# RP2350.net
KiCad netlist of a schematic drawn in Altium Designer
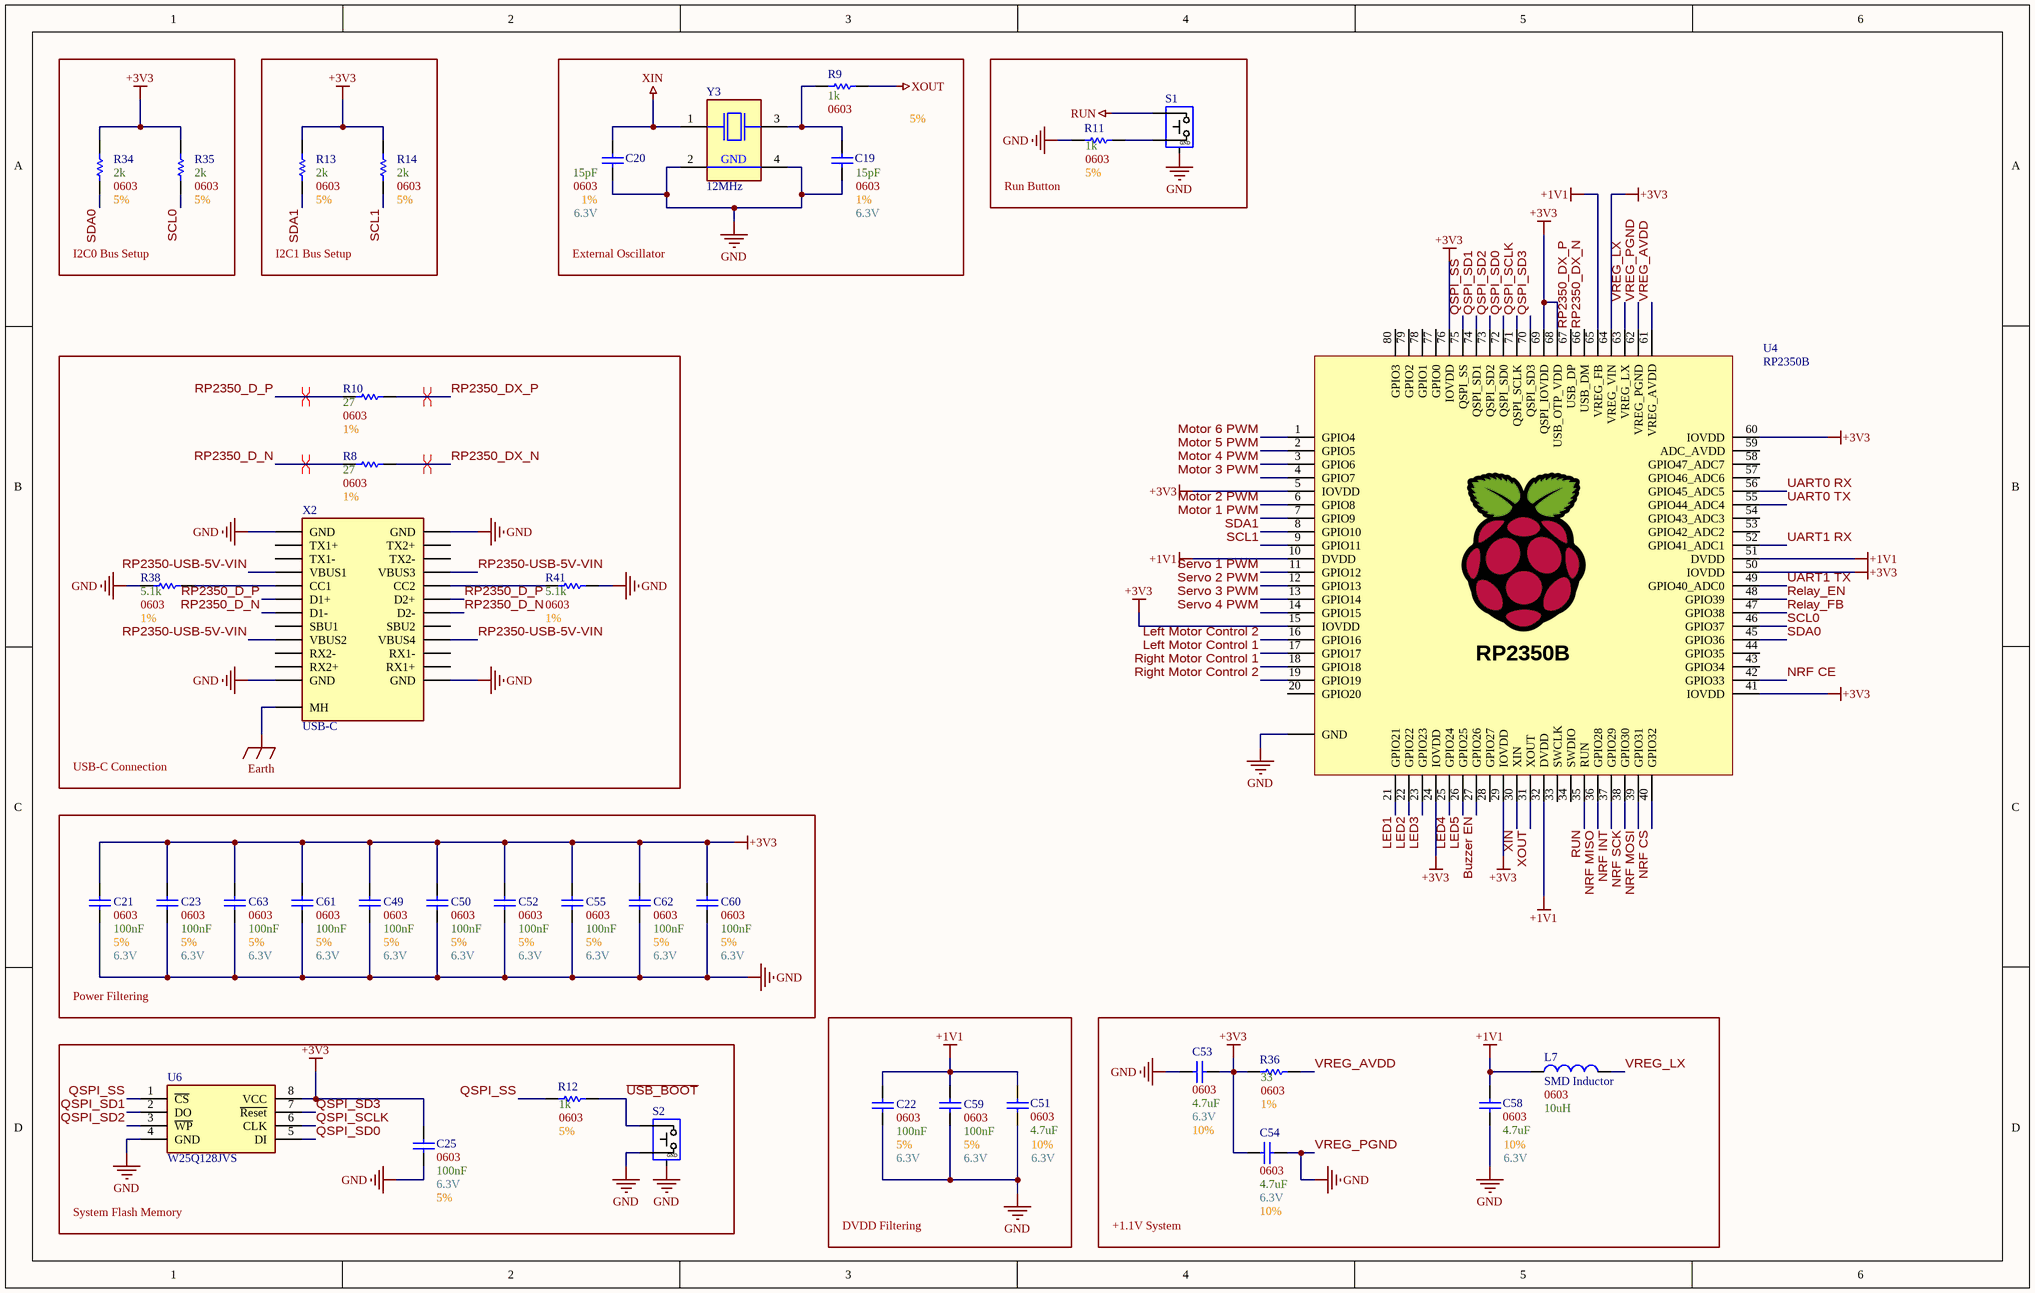
[diagram p0: RP2350.SchDoc]

(export (version "E")
  (design (tool "Eeschema 10.0.6"))
  (components
    (comp (ref "C19")
      (value "[Cap] SMD Nonpolarized")
      (footprint "[Cap] SMD 0603")
      (fields
        (field (name "SIZE PACKAGE") "0603")
        (field (name "CAPACITANCE") "15pF")
        (field (name "VOLTAGE") "6.3V")
        (field (name "TOLERANCE") "1%")
      )
      (libsource (lib "RADM Components") (part "[Cap] SMD Nonpolarized"))
    )
    (comp (ref "C20")
      (value "[Cap] SMD Nonpolarized")
      (footprint "[Cap] SMD 0603")
      (fields
        (field (name "SIZE PACKAGE") "0603")
        (field (name "CAPACITANCE") "15pF")
        (field (name "VOLTAGE") "6.3V")
        (field (name "TOLERANCE") "1%")
      )
      (libsource (lib "RADM Components") (part "[Cap] SMD Nonpolarized"))
    )
    (comp (ref "C21")
      (value "[Cap] SMD Nonpolarized")
      (footprint "[Cap] SMD 0603")
      (fields
        (field (name "SIZE PACKAGE") "0603")
        (field (name "CAPACITANCE") "100nF")
        (field (name "VOLTAGE") "6.3V")
        (field (name "TOLERANCE") "5%")
      )
      (libsource (lib "RADM Components") (part "[Cap] SMD Nonpolarized"))
    )
    (comp (ref "C22")
      (value "[Cap] SMD Nonpolarized")
      (footprint "[Cap] SMD 0603")
      (fields
        (field (name "SIZE PACKAGE") "0603")
        (field (name "CAPACITANCE") "100nF")
        (field (name "VOLTAGE") "6.3V")
        (field (name "TOLERANCE") "5%")
      )
      (libsource (lib "RADM Components") (part "[Cap] SMD Nonpolarized"))
    )
    (comp (ref "C23")
      (value "[Cap] SMD Nonpolarized")
      (footprint "[Cap] SMD 0603")
      (fields
        (field (name "SIZE PACKAGE") "0603")
        (field (name "CAPACITANCE") "100nF")
        (field (name "VOLTAGE") "6.3V")
        (field (name "TOLERANCE") "5%")
      )
      (libsource (lib "RADM Components") (part "[Cap] SMD Nonpolarized"))
    )
    (comp (ref "C25")
      (value "[Cap] SMD Nonpolarized")
      (footprint "[Cap] SMD 0603")
      (fields
        (field (name "SIZE PACKAGE") "0603")
        (field (name "CAPACITANCE") "100nF")
        (field (name "VOLTAGE") "6.3V")
        (field (name "TOLERANCE") "5%")
      )
      (libsource (lib "RADM Components") (part "[Cap] SMD Nonpolarized"))
    )
    (comp (ref "C49")
      (value "[Cap] SMD Nonpolarized")
      (footprint "[Cap] SMD 0603")
      (fields
        (field (name "SIZE PACKAGE") "0603")
        (field (name "CAPACITANCE") "100nF")
        (field (name "VOLTAGE") "6.3V")
        (field (name "TOLERANCE") "5%")
      )
      (libsource (lib "RADM Components") (part "[Cap] SMD Nonpolarized"))
    )
    (comp (ref "C50")
      (value "[Cap] SMD Nonpolarized")
      (footprint "[Cap] SMD 0603")
      (fields
        (field (name "SIZE PACKAGE") "0603")
        (field (name "CAPACITANCE") "100nF")
        (field (name "VOLTAGE") "6.3V")
        (field (name "TOLERANCE") "5%")
      )
      (libsource (lib "RADM Components") (part "[Cap] SMD Nonpolarized"))
    )
    (comp (ref "C51")
      (value "[Cap] SMD Nonpolarized")
      (footprint "[Cap] SMD 0603")
      (fields
        (field (name "SIZE PACKAGE") "0603")
        (field (name "CAPACITANCE") "4.7uF")
        (field (name "VOLTAGE") "6.3V")
        (field (name "TOLERANCE") "10%")
      )
      (libsource (lib "RADM Components") (part "[Cap] SMD Nonpolarized"))
    )
    (comp (ref "C52")
      (value "[Cap] SMD Nonpolarized")
      (footprint "[Cap] SMD 0603")
      (fields
        (field (name "SIZE PACKAGE") "0603")
        (field (name "CAPACITANCE") "100nF")
        (field (name "VOLTAGE") "6.3V")
        (field (name "TOLERANCE") "5%")
      )
      (libsource (lib "RADM Components") (part "[Cap] SMD Nonpolarized"))
    )
    (comp (ref "C53")
      (value "[Cap] SMD Nonpolarized")
      (footprint "[Cap] SMD 0603")
      (fields
        (field (name "SIZE PACKAGE") "0603")
        (field (name "CAPACITANCE") "4.7uF")
        (field (name "VOLTAGE") "6.3V")
        (field (name "TOLERANCE") "10%")
      )
      (libsource (lib "RADM Components") (part "[Cap] SMD Nonpolarized"))
    )
    (comp (ref "C54")
      (value "[Cap] SMD Nonpolarized")
      (footprint "[Cap] SMD 0603")
      (fields
        (field (name "SIZE PACKAGE") "0603")
        (field (name "CAPACITANCE") "4.7uF")
        (field (name "VOLTAGE") "6.3V")
        (field (name "TOLERANCE") "10%")
      )
      (libsource (lib "RADM Components") (part "[Cap] SMD Nonpolarized"))
    )
    (comp (ref "C55")
      (value "[Cap] SMD Nonpolarized")
      (footprint "[Cap] SMD 0603")
      (fields
        (field (name "SIZE PACKAGE") "0603")
        (field (name "CAPACITANCE") "100nF")
        (field (name "VOLTAGE") "6.3V")
        (field (name "TOLERANCE") "5%")
      )
      (libsource (lib "RADM Components") (part "[Cap] SMD Nonpolarized"))
    )
    (comp (ref "C58")
      (value "[Cap] SMD Nonpolarized")
      (footprint "[Cap] SMD 0603")
      (fields
        (field (name "SIZE PACKAGE") "0603")
        (field (name "CAPACITANCE") "4.7uF")
        (field (name "VOLTAGE") "6.3V")
        (field (name "TOLERANCE") "10%")
      )
      (libsource (lib "RADM Components") (part "[Cap] SMD Nonpolarized"))
    )
    (comp (ref "C59")
      (value "[Cap] SMD Nonpolarized")
      (footprint "[Cap] SMD 0603")
      (fields
        (field (name "SIZE PACKAGE") "0603")
        (field (name "CAPACITANCE") "100nF")
        (field (name "VOLTAGE") "6.3V")
        (field (name "TOLERANCE") "5%")
      )
      (libsource (lib "RADM Components") (part "[Cap] SMD Nonpolarized"))
    )
    (comp (ref "C60")
      (value "[Cap] SMD Nonpolarized")
      (footprint "[Cap] SMD 0603")
      (fields
        (field (name "SIZE PACKAGE") "0603")
        (field (name "CAPACITANCE") "100nF")
        (field (name "VOLTAGE") "6.3V")
        (field (name "TOLERANCE") "5%")
      )
      (libsource (lib "RADM Components") (part "[Cap] SMD Nonpolarized"))
    )
    (comp (ref "C61")
      (value "[Cap] SMD Nonpolarized")
      (footprint "[Cap] SMD 0603")
      (fields
        (field (name "SIZE PACKAGE") "0603")
        (field (name "CAPACITANCE") "100nF")
        (field (name "VOLTAGE") "6.3V")
        (field (name "TOLERANCE") "5%")
      )
      (libsource (lib "RADM Components") (part "[Cap] SMD Nonpolarized"))
    )
    (comp (ref "C62")
      (value "[Cap] SMD Nonpolarized")
      (footprint "[Cap] SMD 0603")
      (fields
        (field (name "SIZE PACKAGE") "0603")
        (field (name "CAPACITANCE") "100nF")
        (field (name "VOLTAGE") "6.3V")
        (field (name "TOLERANCE") "5%")
      )
      (libsource (lib "RADM Components") (part "[Cap] SMD Nonpolarized"))
    )
    (comp (ref "C63")
      (value "[Cap] SMD Nonpolarized")
      (footprint "[Cap] SMD 0603")
      (fields
        (field (name "SIZE PACKAGE") "0603")
        (field (name "CAPACITANCE") "100nF")
        (field (name "VOLTAGE") "6.3V")
        (field (name "TOLERANCE") "5%")
      )
      (libsource (lib "RADM Components") (part "[Cap] SMD Nonpolarized"))
    )
    (comp (ref "L7")
      (value "SMD Inductor")
      (footprint "[Inductor] SMD 0603")
      (fields (field (name "SIZE PACKAGE") "0603") (field (name "INDUCTANCE") "10uH"))
      (libsource (lib "RADM Components") (part "[Inductor] SMD Inductor"))
    )
    (comp (ref "R8")
      (value "[Res] SMD Resistor")
      (footprint "[Res] SMD 0603")
      (description "Generic")
      (fields
        (field (name "TOLERANCE") "1%")
        (field (name "RESISTANCE") "27")
        (field (name "SIZE PACKAGE") "0603")
      )
      (libsource (lib "RADM Components") (part "[Res] SMD Resistor"))
    )
    (comp (ref "R9")
      (value "[Res] SMD Resistor")
      (footprint "[Res] SMD 0603")
      (description "Generic")
      (fields
        (field (name "RESISTANCE") "1k")
        (field (name "SIZE PACKAGE") "0603")
        (field (name "TOLERANCE") "5%")
      )
      (libsource (lib "RADM Components") (part "[Res] SMD Resistor"))
    )
    (comp (ref "R10")
      (value "[Res] SMD Resistor")
      (footprint "[Res] SMD 0603")
      (description "Generic")
      (fields
        (field (name "TOLERANCE") "1%")
        (field (name "RESISTANCE") "27")
        (field (name "SIZE PACKAGE") "0603")
      )
      (libsource (lib "RADM Components") (part "[Res] SMD Resistor"))
    )
    (comp (ref "R11")
      (value "[Res] SMD Resistor")
      (footprint "[Res] SMD 0603")
      (description "Generic")
      (fields
        (field (name "RESISTANCE") "1k")
        (field (name "SIZE PACKAGE") "0603")
        (field (name "TOLERANCE") "5%")
      )
      (libsource (lib "RADM Components") (part "[Res] SMD Resistor"))
    )
    (comp (ref "R12")
      (value "[Res] SMD Resistor")
      (footprint "[Res] SMD 0603")
      (description "Generic")
      (fields
        (field (name "RESISTANCE") "1k")
        (field (name "SIZE PACKAGE") "0603")
        (field (name "TOLERANCE") "5%")
      )
      (libsource (lib "RADM Components") (part "[Res] SMD Resistor"))
    )
    (comp (ref "R13")
      (value "[Res] SMD Resistor")
      (footprint "[Res] SMD 0603")
      (description "Generic")
      (fields
        (field (name "RESISTANCE") "2k")
        (field (name "SIZE PACKAGE") "0603")
        (field (name "TOLERANCE") "5%")
      )
      (libsource (lib "RADM Components") (part "[Res] SMD Resistor"))
    )
    (comp (ref "R14")
      (value "[Res] SMD Resistor")
      (footprint "[Res] SMD 0603")
      (description "Generic")
      (fields
        (field (name "RESISTANCE") "2k")
        (field (name "SIZE PACKAGE") "0603")
        (field (name "TOLERANCE") "5%")
      )
      (libsource (lib "RADM Components") (part "[Res] SMD Resistor"))
    )
    (comp (ref "R34")
      (value "[Res] SMD Resistor")
      (footprint "[Res] SMD 0603")
      (description "Generic")
      (fields
        (field (name "RESISTANCE") "2k")
        (field (name "SIZE PACKAGE") "0603")
        (field (name "TOLERANCE") "5%")
      )
      (libsource (lib "RADM Components") (part "[Res] SMD Resistor"))
    )
    (comp (ref "R35")
      (value "[Res] SMD Resistor")
      (footprint "[Res] SMD 0603")
      (description "Generic")
      (fields
        (field (name "RESISTANCE") "2k")
        (field (name "SIZE PACKAGE") "0603")
        (field (name "TOLERANCE") "5%")
      )
      (libsource (lib "RADM Components") (part "[Res] SMD Resistor"))
    )
    (comp (ref "R36")
      (value "[Res] SMD Resistor")
      (footprint "[Res] SMD 0603")
      (description "Generic")
      (fields
        (field (name "RESISTANCE") "33")
        (field (name "SIZE PACKAGE") "0603")
        (field (name "TOLERANCE") "1%")
      )
      (libsource (lib "RADM Components") (part "[Res] SMD Resistor"))
    )
    (comp (ref "R38")
      (value "[Res] SMD Resistor")
      (footprint "[Res] SMD 0603")
      (description "Generic")
      (fields
        (field (name "TOLERANCE") "1%")
        (field (name "RESISTANCE") "5.1k")
        (field (name "SIZE PACKAGE") "0603")
      )
      (libsource (lib "RADM Components") (part "[Res] SMD Resistor"))
    )
    (comp (ref "R41")
      (value "[Res] SMD Resistor")
      (footprint "[Res] SMD 0603")
      (description "Generic")
      (fields
        (field (name "TOLERANCE") "1%")
        (field (name "RESISTANCE") "5.1k")
        (field (name "SIZE PACKAGE") "0603")
      )
      (libsource (lib "RADM Components") (part "[Res] SMD Resistor"))
    )
    (comp (ref "S1")
      (value "[Switch] Pushbutton SMD")
      (footprint "[Switch] Pushbutton SMD 2")
      (libsource (lib "RADM Components") (part "[Switch] Pushbutton SMD"))
    )
    (comp (ref "S2")
      (value "[Switch] Pushbutton SMD")
      (footprint "[Switch] Pushbutton SMD 2")
      (libsource (lib "RADM Components") (part "[Switch] Pushbutton SMD"))
    )
    (comp (ref "U4")
      (value "RP2350B")
      (footprint "[MCU] RP2350B")
      (description "QFN-80 Package")
      (libsource (lib "RADM Components") (part "[MCU] RP2350B"))
    )
    (comp (ref "U6")
      (value "W25Q128JVS")
      (footprint "[Mem] 16Mb Flash Memory")
      (description "W25Q128JVSIQ TR")
      (libsource (lib "RADM Components") (part "[Mem] 16Mb Flash Memory"))
    )
    (comp (ref "X2")
      (value "USB-C")
      (footprint "[Port] USB-C")
      (libsource (lib "RADM Connectors") (part "[Port] USB Type-C"))
    )
    (comp (ref "Y3")
      (value "12MHz")
      (footprint "[XTAL] SMD 12MHz")
      (description "815-ABM8-272-T3")
      (libsource (lib "RADM Components") (part "[XTAL] SMD 12MHz"))
    )
  )
  (nets
    (net (code "1") (name "+1V1") (class "Default")
      (node (ref "C22") (pin "2") (pinfunction "2_2") (pintype "passive"))
      (node (ref "C51") (pin "2") (pinfunction "2_2") (pintype "passive"))
      (node (ref "C58") (pin "2") (pinfunction "2_2") (pintype "passive"))
      (node (ref "C59") (pin "2") (pinfunction "2_2") (pintype "passive"))
      (node (ref "L7") (pin "1") (pinfunction "1_1") (pintype "passive"))
      (node (ref "U4") (pin "10") (pinfunction "DVDD_10") (pintype "passive"))
      (node (ref "U4") (pin "32") (pinfunction "DVDD_32") (pintype "passive"))
      (node (ref "U4") (pin "51") (pinfunction "DVDD_51") (pintype "passive"))
      (node (ref "U4") (pin "65") (pinfunction "VREG_FB_65") (pintype "passive"))
    )
    (net (code "2") (name "+3V3") (class "Default")
      (node (ref "C21") (pin "2") (pinfunction "2_2") (pintype "passive"))
      (node (ref "C23") (pin "2") (pinfunction "2_2") (pintype "passive"))
      (node (ref "C25") (pin "1") (pinfunction "1_1") (pintype "passive"))
      (node (ref "C49") (pin "2") (pinfunction "2_2") (pintype "passive"))
      (node (ref "C50") (pin "2") (pinfunction "2_2") (pintype "passive"))
      (node (ref "C52") (pin "2") (pinfunction "2_2") (pintype "passive"))
      (node (ref "C53") (pin "1") (pinfunction "1_1") (pintype "passive"))
      (node (ref "C54") (pin "2") (pinfunction "2_2") (pintype "passive"))
      (node (ref "C55") (pin "2") (pinfunction "2_2") (pintype "passive"))
      (node (ref "C60") (pin "2") (pinfunction "2_2") (pintype "passive"))
      (node (ref "C61") (pin "2") (pinfunction "2_2") (pintype "passive"))
      (node (ref "C62") (pin "2") (pinfunction "2_2") (pintype "passive"))
      (node (ref "C63") (pin "2") (pinfunction "2_2") (pintype "passive"))
      (node (ref "R13") (pin "2") (pinfunction "2_2") (pintype "passive"))
      (node (ref "R14") (pin "2") (pinfunction "2_2") (pintype "passive"))
      (node (ref "R34") (pin "2") (pinfunction "2_2") (pintype "passive"))
      (node (ref "R35") (pin "2") (pinfunction "2_2") (pintype "passive"))
      (node (ref "R36") (pin "2") (pinfunction "2_2") (pintype "passive"))
      (node (ref "U4") (pin "15") (pinfunction "IOVDD_15") (pintype "passive"))
      (node (ref "U4") (pin "24") (pinfunction "IOVDD_24") (pintype "passive"))
      (node (ref "U4") (pin "29") (pinfunction "IOVDD_29") (pintype "passive"))
      (node (ref "U4") (pin "41") (pinfunction "IOVDD_41") (pintype "passive"))
      (node (ref "U4") (pin "5") (pinfunction "IOVDD_5") (pintype "passive"))
      (node (ref "U4") (pin "50") (pinfunction "IOVDD_50") (pintype "passive"))
      (node (ref "U4") (pin "60") (pinfunction "IOVDD_60") (pintype "passive"))
      (node (ref "U4") (pin "64") (pinfunction "VREG_VIN_64") (pintype "passive"))
      (node (ref "U4") (pin "68") (pinfunction "USB_OTP_VDD_68") (pintype "passive"))
      (node (ref "U4") (pin "69") (pinfunction "QSPI_IOVDD_69") (pintype "passive"))
      (node (ref "U4") (pin "76") (pinfunction "IOVDD_76") (pintype "passive"))
      (node (ref "U6") (pin "8") (pinfunction "VCC_8") (pintype "passive"))
    )
    (net (code "3") (name "/Buzzer EN") (class "Default")
      (node (ref "U4") (pin "27") (pinfunction "GPIO26_27") (pintype "passive"))
    )
    (net (code "4") (name "/LED1") (class "Default")
      (node (ref "U4") (pin "21") (pinfunction "GPIO21_21") (pintype "passive"))
    )
    (net (code "5") (name "/LED2") (class "Default")
      (node (ref "U4") (pin "22") (pinfunction "GPIO22_22") (pintype "passive"))
    )
    (net (code "6") (name "/LED3") (class "Default")
      (node (ref "U4") (pin "23") (pinfunction "GPIO23_23") (pintype "passive"))
    )
    (net (code "7") (name "/LED4") (class "Default")
      (node (ref "U4") (pin "25") (pinfunction "GPIO24_25") (pintype "passive"))
    )
    (net (code "8") (name "/LED5") (class "Default")
      (node (ref "U4") (pin "26") (pinfunction "GPIO25_26") (pintype "passive"))
    )
    (net (code "9") (name "/Left Motor Control 1") (class "Default")
      (node (ref "U4") (pin "17") (pinfunction "GPIO17_17") (pintype "passive"))
    )
    (net (code "10") (name "/Left Motor Control 2") (class "Default")
      (node (ref "U4") (pin "16") (pinfunction "GPIO16_16") (pintype "passive"))
    )
    (net (code "11") (name "/Motor 1 PWM") (class "Default")
      (node (ref "U4") (pin "7") (pinfunction "GPIO9_7") (pintype "passive"))
    )
    (net (code "12") (name "/Motor 2 PWM") (class "Default")
      (node (ref "U4") (pin "6") (pinfunction "GPIO8_6") (pintype "passive"))
    )
    (net (code "13") (name "/Motor 3 PWM") (class "Default")
      (node (ref "U4") (pin "4") (pinfunction "GPIO7_4") (pintype "passive"))
    )
    (net (code "14") (name "/Motor 4 PWM") (class "Default")
      (node (ref "U4") (pin "3") (pinfunction "GPIO6_3") (pintype "passive"))
    )
    (net (code "15") (name "/Motor 5 PWM") (class "Default")
      (node (ref "U4") (pin "2") (pinfunction "GPIO5_2") (pintype "passive"))
    )
    (net (code "16") (name "/Motor 6 PWM") (class "Default")
      (node (ref "U4") (pin "1") (pinfunction "GPIO4_1") (pintype "passive"))
    )
    (net (code "17") (name "/NRF CE") (class "Default")
      (node (ref "U4") (pin "42") (pinfunction "GPIO33_42") (pintype "passive"))
    )
    (net (code "18") (name "/NRF CS") (class "Default")
      (node (ref "U4") (pin "40") (pinfunction "GPIO32_40") (pintype "passive"))
    )
    (net (code "19") (name "/NRF INT") (class "Default")
      (node (ref "U4") (pin "37") (pinfunction "GPIO29_37") (pintype "passive"))
    )
    (net (code "20") (name "/NRF MISO") (class "Default")
      (node (ref "U4") (pin "36") (pinfunction "GPIO28_36") (pintype "passive"))
    )
    (net (code "21") (name "/NRF MOSI") (class "Default")
      (node (ref "U4") (pin "39") (pinfunction "GPIO31_39") (pintype "passive"))
    )
    (net (code "22") (name "/NRF SCK") (class "Default")
      (node (ref "U4") (pin "38") (pinfunction "GPIO30_38") (pintype "passive"))
    )
    (net (code "23") (name "/QSPI_SCLK") (class "Default")
      (node (ref "U4") (pin "71") (pinfunction "QSPI_SCLK_71") (pintype "passive"))
      (node (ref "U6") (pin "6") (pinfunction "CLK_6") (pintype "passive"))
    )
    (net (code "24") (name "/QSPI_SD0") (class "Default")
      (node (ref "U4") (pin "72") (pinfunction "QSPI_SD0_72") (pintype "passive"))
      (node (ref "U6") (pin "5") (pinfunction "DI_5") (pintype "passive"))
    )
    (net (code "25") (name "/QSPI_SD1") (class "Default")
      (node (ref "U4") (pin "74") (pinfunction "QSPI_SD1_74") (pintype "passive"))
      (node (ref "U6") (pin "2") (pinfunction "DO_2") (pintype "passive"))
    )
    (net (code "26") (name "/QSPI_SD2") (class "Default")
      (node (ref "U4") (pin "73") (pinfunction "QSPI_SD2_73") (pintype "passive"))
      (node (ref "U6") (pin "3") (pinfunction "~{WP}_3") (pintype "passive"))
    )
    (net (code "27") (name "/QSPI_SD3") (class "Default")
      (node (ref "U4") (pin "70") (pinfunction "QSPI_SD3_70") (pintype "passive"))
      (node (ref "U6") (pin "7") (pinfunction "~{Reset}_7") (pintype "passive"))
    )
    (net (code "28") (name "/QSPI_SS") (class "Default")
      (node (ref "R12") (pin "2") (pinfunction "2_2") (pintype "passive"))
      (node (ref "U4") (pin "75") (pinfunction "QSPI_SS_75") (pintype "passive"))
      (node (ref "U6") (pin "1") (pinfunction "~{CS}_1") (pintype "passive"))
    )
    (net (code "29") (name "/RP2350-USB-5V-VIN") (class "Default")
      (node (ref "X2") (pin "A4") (pinfunction "VBUS1_A4") (pintype "passive"))
      (node (ref "X2") (pin "A9") (pinfunction "VBUS2_A9") (pintype "passive"))
      (node (ref "X2") (pin "B4") (pinfunction "VBUS3_B4") (pintype "passive"))
      (node (ref "X2") (pin "B9") (pinfunction "VBUS4_B9") (pintype "passive"))
    )
    (net (code "30") (name "/RP2350_DX_N") (class "Default")
      (node (ref "R8") (pin "2") (pinfunction "2_2") (pintype "passive"))
      (node (ref "U4") (pin "66") (pinfunction "USB_DM_66") (pintype "passive"))
    )
    (net (code "31") (name "/RP2350_DX_P") (class "Default")
      (node (ref "R10") (pin "2") (pinfunction "2_2") (pintype "passive"))
      (node (ref "U4") (pin "67") (pinfunction "USB_DP_67") (pintype "passive"))
    )
    (net (code "32") (name "/RP2350_D_N") (class "Default")
      (node (ref "R8") (pin "1") (pinfunction "1_1") (pintype "passive"))
      (node (ref "X2") (pin "A7") (pinfunction "D1-_A7") (pintype "passive"))
      (node (ref "X2") (pin "B7") (pinfunction "D2-_B7") (pintype "passive"))
    )
    (net (code "33") (name "/RP2350_D_P") (class "Default")
      (node (ref "R10") (pin "1") (pinfunction "1_1") (pintype "passive"))
      (node (ref "X2") (pin "A6") (pinfunction "D1+_A6") (pintype "passive"))
      (node (ref "X2") (pin "B6") (pinfunction "D2+_B6") (pintype "passive"))
    )
    (net (code "34") (name "/Relay_EN") (class "Default")
      (node (ref "U4") (pin "48") (pinfunction "GPIO39_48") (pintype "passive"))
    )
    (net (code "35") (name "/Relay_FB") (class "Default")
      (node (ref "U4") (pin "47") (pinfunction "GPIO38_47") (pintype "passive"))
    )
    (net (code "36") (name "/Right Motor Control 1") (class "Default")
      (node (ref "U4") (pin "18") (pinfunction "GPIO18_18") (pintype "passive"))
    )
    (net (code "37") (name "/Right Motor Control 2") (class "Default")
      (node (ref "U4") (pin "19") (pinfunction "GPIO19_19") (pintype "passive"))
    )
    (net (code "38") (name "/SCL0") (class "Default")
      (node (ref "R35") (pin "1") (pinfunction "1_1") (pintype "passive"))
      (node (ref "U4") (pin "46") (pinfunction "GPIO37_46") (pintype "passive"))
    )
    (net (code "39") (name "/SCL1") (class "Default")
      (node (ref "R14") (pin "1") (pinfunction "1_1") (pintype "passive"))
      (node (ref "U4") (pin "9") (pinfunction "GPIO11_9") (pintype "passive"))
    )
    (net (code "40") (name "/SDA0") (class "Default")
      (node (ref "R34") (pin "1") (pinfunction "1_1") (pintype "passive"))
      (node (ref "U4") (pin "45") (pinfunction "GPIO36_45") (pintype "passive"))
    )
    (net (code "41") (name "/SDA1") (class "Default")
      (node (ref "R13") (pin "1") (pinfunction "1_1") (pintype "passive"))
      (node (ref "U4") (pin "8") (pinfunction "GPIO10_8") (pintype "passive"))
    )
    (net (code "42") (name "/Servo 1 PWM") (class "Default")
      (node (ref "U4") (pin "11") (pinfunction "GPIO12_11") (pintype "passive"))
    )
    (net (code "43") (name "/Servo 2 PWM") (class "Default")
      (node (ref "U4") (pin "12") (pinfunction "GPIO13_12") (pintype "passive"))
    )
    (net (code "44") (name "/Servo 3 PWM") (class "Default")
      (node (ref "U4") (pin "13") (pinfunction "GPIO14_13") (pintype "passive"))
    )
    (net (code "45") (name "/Servo 4 PWM") (class "Default")
      (node (ref "U4") (pin "14") (pinfunction "GPIO15_14") (pintype "passive"))
    )
    (net (code "46") (name "/UART0 RX") (class "Default")
      (node (ref "U4") (pin "56") (pinfunction "GPIO45_ADC5_56") (pintype "passive"))
    )
    (net (code "47") (name "/UART0 TX") (class "Default")
      (node (ref "U4") (pin "55") (pinfunction "GPIO44_ADC4_55") (pintype "passive"))
    )
    (net (code "48") (name "/UART1 RX") (class "Default")
      (node (ref "U4") (pin "52") (pinfunction "GPIO41_ADC1_52") (pintype "passive"))
    )
    (net (code "49") (name "/UART1 TX") (class "Default")
      (node (ref "U4") (pin "49") (pinfunction "GPIO40_ADC0_49") (pintype "passive"))
    )
    (net (code "50") (name "/VREG_AVDD") (class "Default")
      (node (ref "R36") (pin "1") (pinfunction "1_1") (pintype "passive"))
      (node (ref "U4") (pin "61") (pinfunction "VREG_AVDD_61") (pintype "passive"))
    )
    (net (code "51") (name "/VREG_LX") (class "Default")
      (node (ref "L7") (pin "2") (pinfunction "2_2") (pintype "passive"))
      (node (ref "U4") (pin "63") (pinfunction "VREG_LX_63") (pintype "passive"))
    )
    (net (code "52") (name "/~{USB_BOOT}") (class "Default")
      (node (ref "R12") (pin "1") (pinfunction "1_1") (pintype "passive"))
      (node (ref "S2") (pin "1") (pintype "power_in"))
    )
    (net (code "53") (name "Earth") (class "Default")
      (node (ref "X2") (pin "MH") (pinfunction "MH_MH") (pintype "passive"))
    )
    (net (code "54") (name "GND") (class "Default")
      (node (ref "C19") (pin "1") (pinfunction "1_1") (pintype "passive"))
      (node (ref "C20") (pin "1") (pinfunction "1_1") (pintype "passive"))
      (node (ref "C21") (pin "1") (pinfunction "1_1") (pintype "passive"))
      (node (ref "C22") (pin "1") (pinfunction "1_1") (pintype "passive"))
      (node (ref "C23") (pin "1") (pinfunction "1_1") (pintype "passive"))
      (node (ref "C25") (pin "2") (pinfunction "2_2") (pintype "passive"))
      (node (ref "C49") (pin "1") (pinfunction "1_1") (pintype "passive"))
      (node (ref "C50") (pin "1") (pinfunction "1_1") (pintype "passive"))
      (node (ref "C51") (pin "1") (pinfunction "1_1") (pintype "passive"))
      (node (ref "C52") (pin "1") (pinfunction "1_1") (pintype "passive"))
      (node (ref "C53") (pin "2") (pinfunction "2_2") (pintype "passive"))
      (node (ref "C54") (pin "1") (pinfunction "1_1") (pintype "passive"))
      (node (ref "C55") (pin "1") (pinfunction "1_1") (pintype "passive"))
      (node (ref "C58") (pin "1") (pinfunction "1_1") (pintype "passive"))
      (node (ref "C59") (pin "1") (pinfunction "1_1") (pintype "passive"))
      (node (ref "C60") (pin "1") (pinfunction "1_1") (pintype "passive"))
      (node (ref "C61") (pin "1") (pinfunction "1_1") (pintype "passive"))
      (node (ref "C62") (pin "1") (pinfunction "1_1") (pintype "passive"))
      (node (ref "C63") (pin "1") (pinfunction "1_1") (pintype "passive"))
      (node (ref "R11") (pin "2") (pinfunction "2_2") (pintype "passive"))
      (node (ref "R38") (pin "1") (pinfunction "1_1") (pintype "passive"))
      (node (ref "R41") (pin "2") (pinfunction "2_2") (pintype "passive"))
      (node (ref "S1") (pin "GND") (pinfunction "GND_GND") (pintype "power_in"))
      (node (ref "S2") (pin "2") (pintype "power_in"))
      (node (ref "S2") (pin "GND") (pinfunction "GND_GND") (pintype "power_in"))
      (node (ref "U4") (pin "62") (pinfunction "VREG_PGND_62") (pintype "passive"))
      (node (ref "U4") (pin "Pad") (pinfunction "GND_Pad") (pintype "passive"))
      (node (ref "U6") (pin "4") (pinfunction "GND_4") (pintype "passive"))
      (node (ref "X2") (pin "A1") (pinfunction "GND_A1") (pintype "passive"))
      (node (ref "X2") (pin "A12") (pinfunction "GND_A12") (pintype "passive"))
      (node (ref "X2") (pin "B1") (pinfunction "GND_B1") (pintype "passive"))
      (node (ref "X2") (pin "B12") (pinfunction "GND_B12") (pintype "passive"))
      (node (ref "Y3") (pin "2") (pinfunction "GND_2") (pintype "power_in"))
      (node (ref "Y3") (pin "4") (pinfunction "GND_4") (pintype "power_in"))
    )
    (net (code "55") (name "Net-(R11-Pad1)") (class "Default")
      (node (ref "R11") (pin "1") (pinfunction "1_1") (pintype "passive"))
      (node (ref "S1") (pin "2") (pintype "power_in"))
    )
    (net (code "56") (name "Net-(X2-CC1)") (class "Default")
      (node (ref "R38") (pin "2") (pinfunction "2_2") (pintype "passive"))
      (node (ref "X2") (pin "A5") (pinfunction "CC1_A5") (pintype "passive"))
    )
    (net (code "57") (name "Net-(X2-CC2)") (class "Default")
      (node (ref "R41") (pin "1") (pinfunction "1_1") (pintype "passive"))
      (node (ref "X2") (pin "B5") (pinfunction "CC2_B5") (pintype "passive"))
    )
    (net (code "58") (name "Net-(Y3-XTAL2)") (class "Default")
      (node (ref "C19") (pin "2") (pinfunction "2_2") (pintype "passive"))
      (node (ref "R9") (pin "2") (pinfunction "2_2") (pintype "passive"))
      (node (ref "Y3") (pin "3") (pinfunction "XTAL2_3") (pintype "power_in"))
    )
    (net (code "59") (name "RUN") (class "Default")
      (node (ref "S1") (pin "1") (pintype "power_in"))
      (node (ref "U4") (pin "35") (pinfunction "RUN_35") (pintype "passive"))
    )
    (net (code "60") (name "XIN") (class "Default")
      (node (ref "C20") (pin "2") (pinfunction "2_2") (pintype "passive"))
      (node (ref "U4") (pin "30") (pinfunction "XIN_30") (pintype "passive"))
      (node (ref "Y3") (pin "1") (pinfunction "XTAL1_1") (pintype "power_in"))
    )
    (net (code "61") (name "XOUT") (class "Default")
      (node (ref "R9") (pin "1") (pinfunction "1_1") (pintype "passive"))
      (node (ref "U4") (pin "31") (pinfunction "XOUT_31") (pintype "passive"))
    )
    (net (code "62") (name "unconnected-(U4-ADC_AVDD-Pad59)") (class "Default")
      (node (ref "U4") (pin "59") (pinfunction "ADC_AVDD_59") (pintype "passive"))
    )
    (net (code "63") (name "unconnected-(U4-GPIO0-Pad77)") (class "Default")
      (node (ref "U4") (pin "77") (pinfunction "GPIO0_77") (pintype "passive"))
    )
    (net (code "64") (name "unconnected-(U4-GPIO1-Pad78)") (class "Default")
      (node (ref "U4") (pin "78") (pinfunction "GPIO1_78") (pintype "passive"))
    )
    (net (code "65") (name "unconnected-(U4-GPIO2-Pad79)") (class "Default")
      (node (ref "U4") (pin "79") (pinfunction "GPIO2_79") (pintype "passive"))
    )
    (net (code "66") (name "unconnected-(U4-GPIO3-Pad80)") (class "Default")
      (node (ref "U4") (pin "80") (pinfunction "GPIO3_80") (pintype "passive"))
    )
    (net (code "67") (name "unconnected-(U4-GPIO20-Pad20)") (class "Default")
      (node (ref "U4") (pin "20") (pinfunction "GPIO20_20") (pintype "passive"))
    )
    (net (code "68") (name "unconnected-(U4-GPIO27-Pad28)") (class "Default")
      (node (ref "U4") (pin "28") (pinfunction "GPIO27_28") (pintype "passive"))
    )
    (net (code "69") (name "unconnected-(U4-GPIO34-Pad43)") (class "Default")
      (node (ref "U4") (pin "43") (pinfunction "GPIO34_43") (pintype "passive"))
    )
    (net (code "70") (name "unconnected-(U4-GPIO35-Pad44)") (class "Default")
      (node (ref "U4") (pin "44") (pinfunction "GPIO35_44") (pintype "passive"))
    )
    (net (code "71") (name "unconnected-(U4-GPIO42_ADC2-Pad53)") (class "Default")
      (node (ref "U4") (pin "53") (pinfunction "GPIO42_ADC2_53") (pintype "passive"))
    )
    (net (code "72") (name "unconnected-(U4-GPIO43_ADC3-Pad54)") (class "Default")
      (node (ref "U4") (pin "54") (pinfunction "GPIO43_ADC3_54") (pintype "passive"))
    )
    (net (code "73") (name "unconnected-(U4-GPIO46_ADC6-Pad57)") (class "Default")
      (node (ref "U4") (pin "57") (pinfunction "GPIO46_ADC6_57") (pintype "passive"))
    )
    (net (code "74") (name "unconnected-(U4-GPIO47_ADC7-Pad58)") (class "Default")
      (node (ref "U4") (pin "58") (pinfunction "GPIO47_ADC7_58") (pintype "passive"))
    )
    (net (code "75") (name "unconnected-(U4-SWCLK-Pad33)") (class "Default")
      (node (ref "U4") (pin "33") (pinfunction "SWCLK_33") (pintype "passive"))
    )
    (net (code "76") (name "unconnected-(U4-SWDIO-Pad34)") (class "Default")
      (node (ref "U4") (pin "34") (pinfunction "SWDIO_34") (pintype "passive"))
    )
    (net (code "77") (name "unconnected-(X2-RX1+-PadB11)") (class "Default")
      (node (ref "X2") (pin "B11") (pinfunction "RX1+_B11") (pintype "passive"))
    )
    (net (code "78") (name "unconnected-(X2-RX1--PadB10)") (class "Default")
      (node (ref "X2") (pin "B10") (pinfunction "RX1-_B10") (pintype "passive"))
    )
    (net (code "79") (name "unconnected-(X2-RX2+-PadA11)") (class "Default")
      (node (ref "X2") (pin "A11") (pinfunction "RX2+_A11") (pintype "passive"))
    )
    (net (code "80") (name "unconnected-(X2-RX2--PadA10)") (class "Default")
      (node (ref "X2") (pin "A10") (pinfunction "RX2-_A10") (pintype "passive"))
    )
    (net (code "81") (name "unconnected-(X2-SBU1-PadA8)") (class "Default")
      (node (ref "X2") (pin "A8") (pinfunction "SBU1_A8") (pintype "passive"))
    )
    (net (code "82") (name "unconnected-(X2-SBU2-PadB8)") (class "Default")
      (node (ref "X2") (pin "B8") (pinfunction "SBU2_B8") (pintype "passive"))
    )
    (net (code "83") (name "unconnected-(X2-TX1+-PadA2)") (class "Default")
      (node (ref "X2") (pin "A2") (pinfunction "TX1+_A2") (pintype "passive"))
    )
    (net (code "84") (name "unconnected-(X2-TX1--PadA3)") (class "Default")
      (node (ref "X2") (pin "A3") (pinfunction "TX1-_A3") (pintype "passive"))
    )
    (net (code "85") (name "unconnected-(X2-TX2+-PadB2)") (class "Default")
      (node (ref "X2") (pin "B2") (pinfunction "TX2+_B2") (pintype "passive"))
    )
    (net (code "86") (name "unconnected-(X2-TX2--PadB3)") (class "Default")
      (node (ref "X2") (pin "B3") (pinfunction "TX2-_B3") (pintype "passive"))
    )
  )
)
